# MP2456_EVM_V1-eagle_7_6.net
KiCad netlist of a schematic drawn in EAGLE
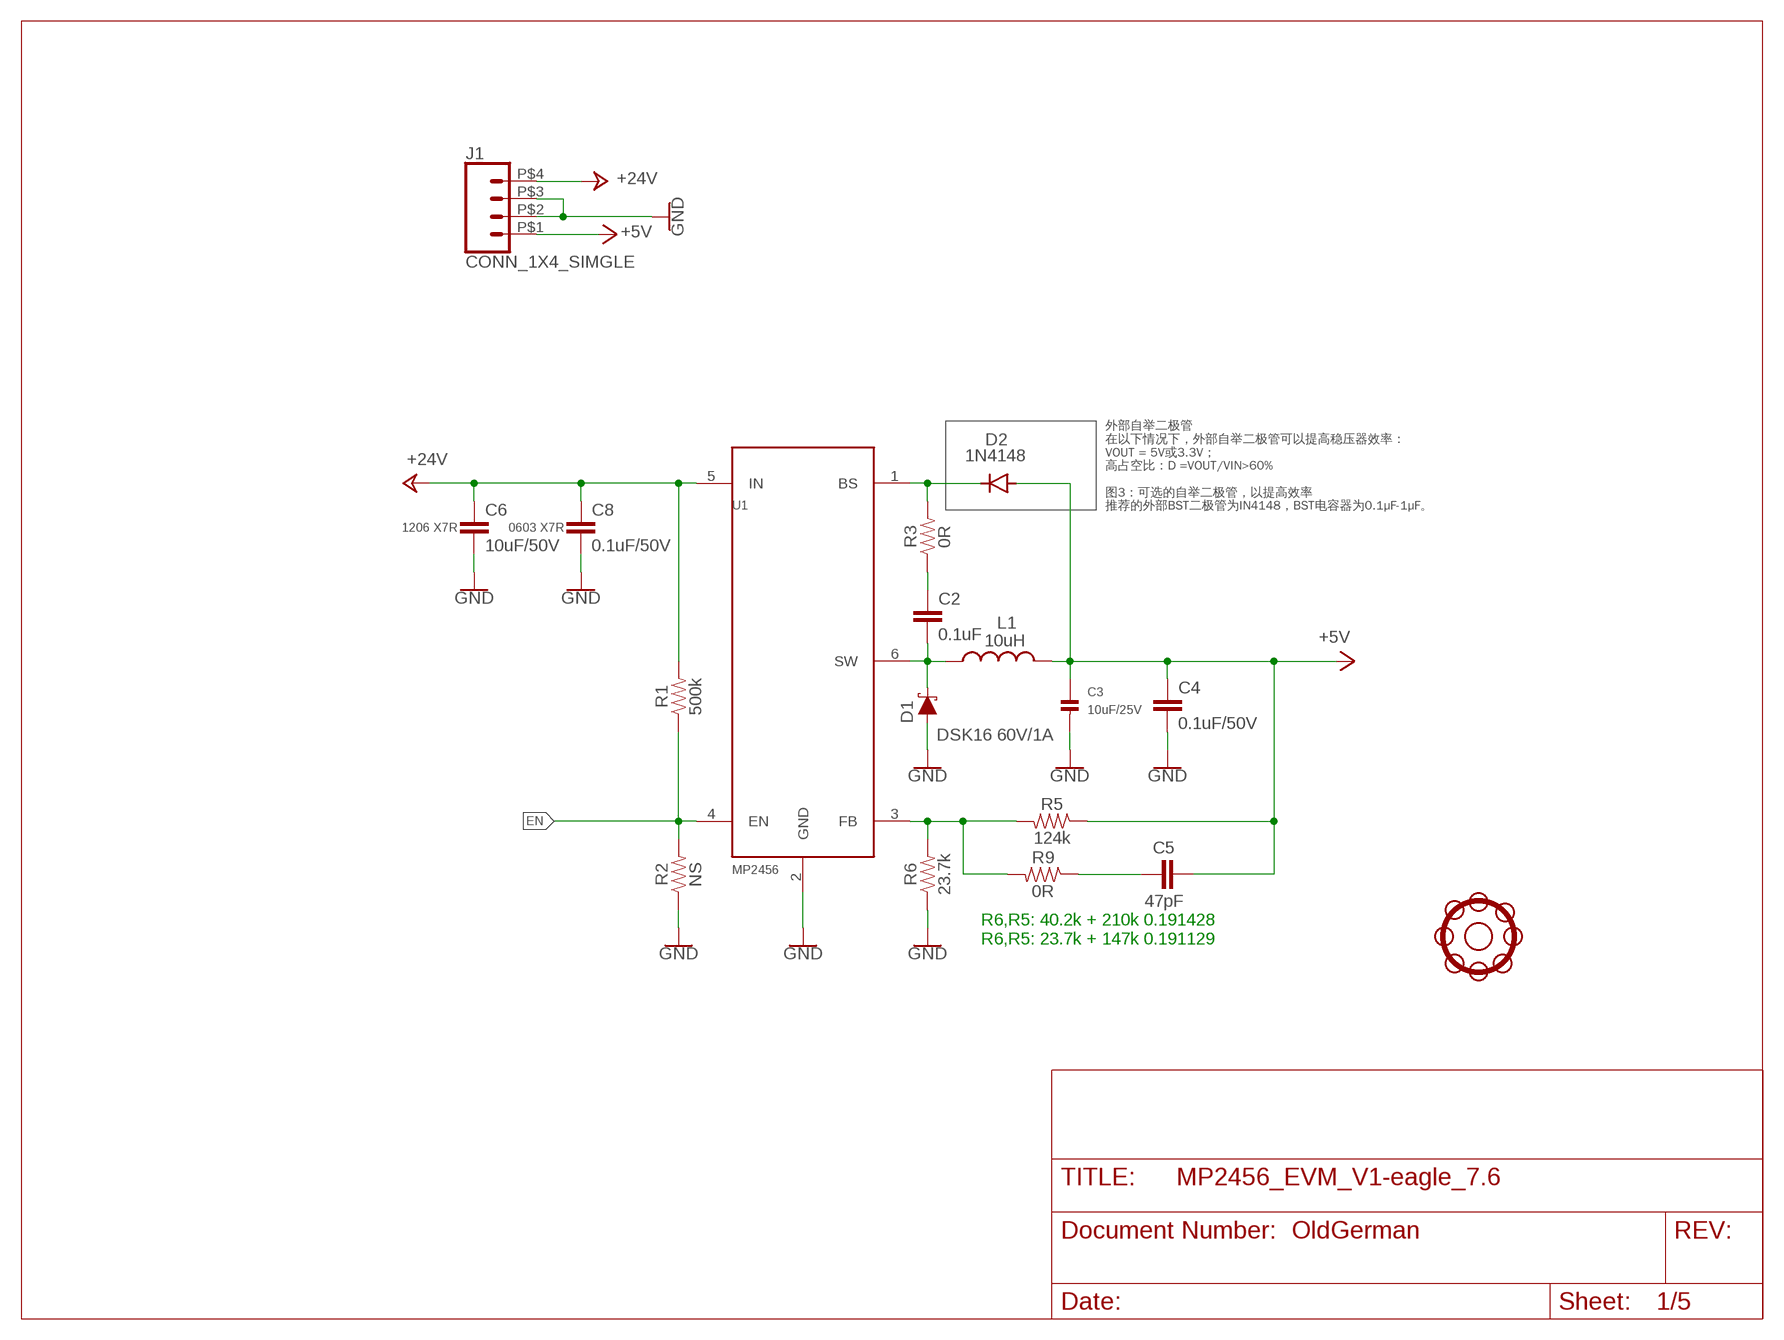
[diagram p0: schematic, sheet 1]

(export (version "E")
  (design (tool "Eeschema 10.0.6"))
  (components
    (comp (ref "C2")
      (value "0.1uF")
      (footprint "eagle-import:0603")
      (libsource (lib "eagle-import") (part "CAP-0603"))
    )
    (comp (ref "C3")
      (value "10uF/25V")
      (footprint "eagle-import:_0805MP")
      (libsource (lib "eagle-import") (part "CAP_CERAMIC_0805MP"))
    )
    (comp (ref "C4")
      (value "0.1uF/50V")
      (footprint "eagle-import:0603")
      (libsource (lib "eagle-import") (part "CAP-0603"))
    )
    (comp (ref "C5")
      (value "47pF")
      (footprint "eagle-import:0603")
      (libsource (lib "eagle-import") (part "CAP-0603"))
    )
    (comp (ref "C6")
      (value "10uF/50V")
      (footprint "eagle-import:1206")
      (libsource (lib "eagle-import") (part "CAP-1206"))
    )
    (comp (ref "C8")
      (value "0.1uF/50V")
      (footprint "eagle-import:0603")
      (libsource (lib "eagle-import") (part "CAP-0603"))
    )
    (comp (ref "D1")
      (value "DSK16 60V/1A")
      (footprint "eagle-import:SOD123")
      (libsource (lib "eagle-import") (part "B5819W-SOD123"))
    )
    (comp (ref "D2")
      (value "1N4148")
      (footprint "eagle-import:SOD123")
      (libsource (lib "eagle-import") (part "DIODE-SOD123"))
    )
    (comp (ref "J1")
      (value "CONN_1X4_SIMGLE")
      (footprint "eagle-import:CONN_1X04_SINGLE")
      (libsource (lib "eagle-import") (part "CONN_1X4_SIMGLE"))
    )
    (comp (ref "L1")
      (value "10uH")
      (footprint "eagle-import:4020TYPE")
      (libsource (lib "eagle-import") (part "INDUCTOR_4040"))
    )
    (comp (ref "R1")
      (value "500k")
      (footprint "eagle-import:0603")
      (libsource (lib "eagle-import") (part "RESISTOR0603"))
    )
    (comp (ref "R2")
      (value "NS")
      (footprint "eagle-import:0603")
      (libsource (lib "eagle-import") (part "RESISTOR0603"))
    )
    (comp (ref "R3")
      (value "0R")
      (footprint "eagle-import:0603")
      (libsource (lib "eagle-import") (part "RESISTOR0603"))
    )
    (comp (ref "R5")
      (value "124k")
      (footprint "eagle-import:0603")
      (libsource (lib "eagle-import") (part "RESISTOR0603"))
    )
    (comp (ref "R6")
      (value "23.7k")
      (footprint "eagle-import:0603")
      (libsource (lib "eagle-import") (part "RESISTOR0603"))
    )
    (comp (ref "R9")
      (value "0R")
      (footprint "eagle-import:0603")
      (libsource (lib "eagle-import") (part "RESISTOR0603"))
    )
    (comp (ref "U$1")
      (value "SUN_HOLE_M3")
      (footprint "eagle-import:SUN_HOLE_M3")
      (libsource (lib "eagle-import") (part "SUN_HOLE_M3"))
    )
    (comp (ref "U1")
      (value "MP2456")
      (footprint "eagle-import:SOT23-6")
      (libsource (lib "eagle-import") (part "MP2456"))
    )
  )
  (nets
    (net (code "1") (name "+5V") (class "Default")
      (node (ref "C3") (pin "1") (pinfunction "P$1_1") (pintype "passive"))
      (node (ref "C4") (pin "1") (pinfunction "1_1") (pintype "passive"))
      (node (ref "C5") (pin "2") (pinfunction "2_2") (pintype "passive"))
      (node (ref "D2") (pin "A") (pinfunction "A_A") (pintype "passive"))
      (node (ref "J1") (pin "P$1") (pinfunction "1_P$1") (pintype "passive"))
      (node (ref "L1") (pin "P$2") (pinfunction "2_P$2") (pintype "passive"))
      (node (ref "R5") (pin "1") (pinfunction "1_1") (pintype "passive"))
    )
    (net (code "2") (name "+24V") (class "Default")
      (node (ref "C6") (pin "1") (pinfunction "1_1") (pintype "passive"))
      (node (ref "C8") (pin "1") (pinfunction "1_1") (pintype "passive"))
      (node (ref "J1") (pin "P$4") (pinfunction "4_P$4") (pintype "passive"))
      (node (ref "R1") (pin "2") (pinfunction "2_2") (pintype "passive"))
      (node (ref "U1") (pin "5") (pinfunction "IN_5") (pintype "bidirectional"))
    )
    (net (code "3") (name "EN") (class "Default")
      (node (ref "R1") (pin "1") (pinfunction "1_1") (pintype "passive"))
      (node (ref "R2") (pin "2") (pinfunction "2_2") (pintype "passive"))
      (node (ref "U1") (pin "4") (pinfunction "EN_4") (pintype "bidirectional"))
    )
    (net (code "4") (name "GND") (class "Default")
      (node (ref "C3") (pin "2") (pinfunction "P$2_2") (pintype "passive"))
      (node (ref "C4") (pin "2") (pinfunction "2_2") (pintype "passive"))
      (node (ref "C6") (pin "2") (pinfunction "2_2") (pintype "passive"))
      (node (ref "C8") (pin "2") (pinfunction "2_2") (pintype "passive"))
      (node (ref "D1") (pin "A") (pinfunction "A_A") (pintype "passive"))
      (node (ref "J1") (pin "P$2") (pinfunction "2_P$2") (pintype "passive"))
      (node (ref "J1") (pin "P$3") (pinfunction "3_P$3") (pintype "passive"))
      (node (ref "R2") (pin "1") (pinfunction "1_1") (pintype "passive"))
      (node (ref "R6") (pin "1") (pinfunction "1_1") (pintype "passive"))
      (node (ref "U1") (pin "2") (pinfunction "GND_2") (pintype "bidirectional"))
    )
    (net (code "5") (name "Net-(C2-Pad1)") (class "Default")
      (node (ref "C2") (pin "1") (pinfunction "1_1") (pintype "passive"))
      (node (ref "R3") (pin "1") (pinfunction "1_1") (pintype "passive"))
    )
    (net (code "6") (name "Net-(C5-Pad1)") (class "Default")
      (node (ref "C5") (pin "1") (pinfunction "1_1") (pintype "passive"))
      (node (ref "R9") (pin "1") (pinfunction "1_1") (pintype "passive"))
    )
    (net (code "7") (name "Net-(L1-1)") (class "Default")
      (node (ref "C2") (pin "2") (pinfunction "2_2") (pintype "passive"))
      (node (ref "D1") (pin "C") (pinfunction "C_C") (pintype "passive"))
      (node (ref "L1") (pin "P$1") (pinfunction "1_P$1") (pintype "passive"))
      (node (ref "U1") (pin "6") (pinfunction "SW_6") (pintype "bidirectional"))
    )
    (net (code "8") (name "Net-(U1-BS)") (class "Default")
      (node (ref "D2") (pin "C") (pinfunction "C_C") (pintype "passive"))
      (node (ref "R3") (pin "2") (pinfunction "2_2") (pintype "passive"))
      (node (ref "U1") (pin "1") (pinfunction "BS_1") (pintype "bidirectional"))
    )
    (net (code "9") (name "Net-(U1-FB)") (class "Default")
      (node (ref "R5") (pin "2") (pinfunction "2_2") (pintype "passive"))
      (node (ref "R6") (pin "2") (pinfunction "2_2") (pintype "passive"))
      (node (ref "R9") (pin "2") (pinfunction "2_2") (pintype "passive"))
      (node (ref "U1") (pin "3") (pinfunction "FB_3") (pintype "bidirectional"))
    )
  )
)
